# KeyboardPower.net
KiCad netlist of a schematic drawn in EAGLE
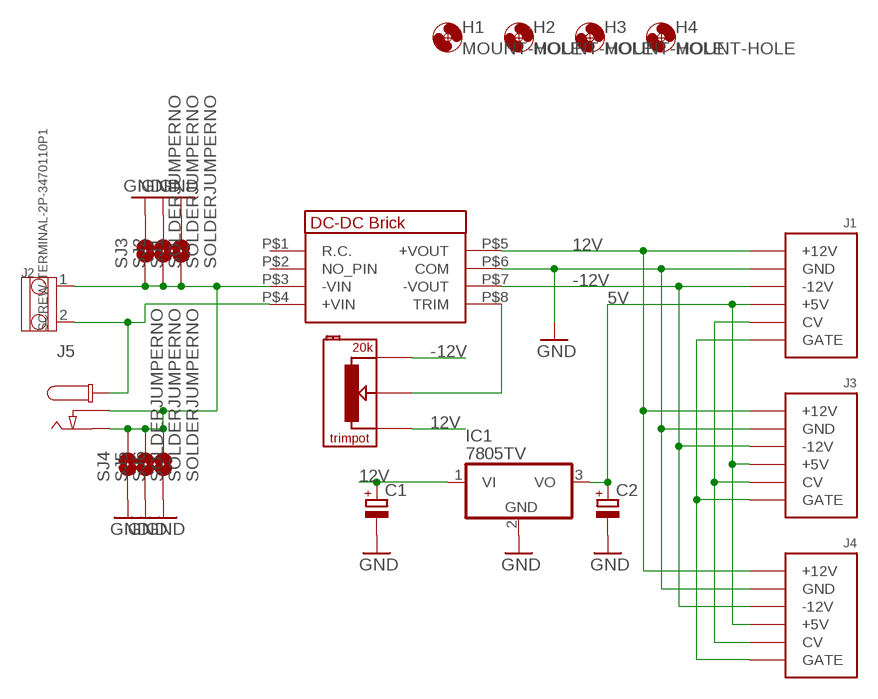
[diagram p0: schematic, sheet 1]

(export (version "E")
  (design (tool "Eeschema 10.0.6"))
  (components
    (comp (ref "C1")
      (value "CAPACITOR_POL-CASE_B")
      (footprint "eagle-import:CASE_B")
      (libsource (lib "eagle-import") (part "CAPACITOR_POL-CASE_B"))
    )
    (comp (ref "C2")
      (value "CAPACITOR_POL-CASE_B")
      (footprint "eagle-import:CASE_B")
      (libsource (lib "eagle-import") (part "CAPACITOR_POL-CASE_B"))
    )
    (comp (ref "H1")
      (value "MOUNT-HOLE")
      (footprint "eagle-import:3.2-NOMARKINGS-SMALLSAFEZONE")
      (libsource (lib "eagle-import") (part "MOUNT-HOLE"))
    )
    (comp (ref "H2")
      (value "MOUNT-HOLE")
      (footprint "eagle-import:3.2-NOMARKINGS-SMALLSAFEZONE")
      (libsource (lib "eagle-import") (part "MOUNT-HOLE"))
    )
    (comp (ref "H3")
      (value "MOUNT-HOLE")
      (footprint "eagle-import:3.2-NOMARKINGS-SMALLSAFEZONE")
      (libsource (lib "eagle-import") (part "MOUNT-HOLE"))
    )
    (comp (ref "H4")
      (value "MOUNT-HOLE")
      (footprint "eagle-import:3.2-NOMARKINGS-SMALLSAFEZONE")
      (libsource (lib "eagle-import") (part "MOUNT-HOLE"))
    )
    (comp (ref "IC1")
      (value "7805TV")
      (footprint "eagle-import:TO220V")
      (libsource (lib "eagle-import") (part "78TV05"))
    )
    (comp (ref "J1")
      (value "POWERSHROUDED")
      (footprint "eagle-import:POWER_16_SHROUDED")
      (libsource (lib "eagle-import") (part "POWERSHROUDED"))
    )
    (comp (ref "J2")
      (value "SCREW-TERMINAL-2P-3470110P1")
      (footprint "eagle-import:2P-5.0")
      (libsource (lib "eagle-import") (part "SCREW-TERMINAL-2P-3470110P1"))
    )
    (comp (ref "J3")
      (value "POWER_SHROUDED_NOTEXT")
      (footprint "eagle-import:POWER_16_SHROUDED_NOTEXT")
      (libsource (lib "eagle-import") (part "POWER_SHROUDED_NOTEXT"))
    )
    (comp (ref "J4")
      (value "POWER_SHROUDED_NOTEXT")
      (footprint "eagle-import:POWER_16_SHROUDED_NOTEXT")
      (libsource (lib "eagle-import") (part "POWER_SHROUDED_NOTEXT"))
    )
    (comp (ref "J5")
      (value "CON_DC_M-DC_PTH2")
      (footprint "eagle-import:DC_BARREL_JACK_PTH_2MM_2")
      (libsource (lib "eagle-import") (part "CON_DC_M-DC_PTH2"))
    )
    (comp (ref "R1")
      (value "20k")
      (footprint "eagle-import:TRIMPOT")
      (libsource (lib "eagle-import") (part "TRIMPOT"))
    )
    (comp (ref "SJ1")
      (value "SOLDERJUMPERNO")
      (footprint "eagle-import:SJ_2S-NO")
      (libsource (lib "eagle-import") (part "SOLDERJUMPERNO"))
    )
    (comp (ref "SJ2")
      (value "SOLDERJUMPERNO")
      (footprint "eagle-import:SJ_2S-NO")
      (libsource (lib "eagle-import") (part "SOLDERJUMPERNO"))
    )
    (comp (ref "SJ3")
      (value "SOLDERJUMPERNO")
      (footprint "eagle-import:SJ_2S-NO")
      (libsource (lib "eagle-import") (part "SOLDERJUMPERNO"))
    )
    (comp (ref "SJ4")
      (value "SOLDERJUMPERNO")
      (footprint "eagle-import:SJ_2S-NO")
      (libsource (lib "eagle-import") (part "SOLDERJUMPERNO"))
    )
    (comp (ref "SJ5")
      (value "SOLDERJUMPERNO")
      (footprint "eagle-import:SJ_2S-NO")
      (libsource (lib "eagle-import") (part "SOLDERJUMPERNO"))
    )
    (comp (ref "SJ6")
      (value "SOLDERJUMPERNO")
      (footprint "eagle-import:SJ_2S-NO")
      (libsource (lib "eagle-import") (part "SOLDERJUMPERNO"))
    )
    (comp (ref "U$1")
      (value "DKA30")
      (footprint "eagle-import:MEANWELL_DKA30")
      (libsource (lib "eagle-import") (part "DKA30"))
    )
  )
  (nets
    (net (code "1") (name "/-12V") (class "Default")
      (node (ref "J1") (pin "1") (pinfunction "-12V_1") (pintype "bidirectional"))
      (node (ref "J1") (pin "2") (pinfunction "-12V_2") (pintype "bidirectional"))
      (node (ref "J3") (pin "1") (pinfunction "-12V_1") (pintype "bidirectional"))
      (node (ref "J3") (pin "2") (pinfunction "-12V_2") (pintype "bidirectional"))
      (node (ref "J4") (pin "1") (pinfunction "-12V_1") (pintype "bidirectional"))
      (node (ref "J4") (pin "2") (pinfunction "-12V_2") (pintype "bidirectional"))
      (node (ref "R1") (pin "P$3") (pinfunction "P$3_P$3") (pintype "bidirectional"))
      (node (ref "U$1") (pin "P$7") (pinfunction "-VOUT_P$7") (pintype "bidirectional"))
    )
    (net (code "2") (name "/5V") (class "Default")
      (node (ref "C2") (pin "+") (pinfunction "+_+") (pintype "passive"))
      (node (ref "IC1") (pin "3") (pinfunction "VO_3") (pintype "passive"))
      (node (ref "J1") (pin "11") (pinfunction "+5V_11") (pintype "bidirectional"))
      (node (ref "J1") (pin "12") (pinfunction "+5V_12") (pintype "bidirectional"))
      (node (ref "J3") (pin "11") (pinfunction "+5V_11") (pintype "bidirectional"))
      (node (ref "J3") (pin "12") (pinfunction "+5V_12") (pintype "bidirectional"))
      (node (ref "J4") (pin "11") (pinfunction "+5V_11") (pintype "bidirectional"))
      (node (ref "J4") (pin "12") (pinfunction "+5V_12") (pintype "bidirectional"))
    )
    (net (code "3") (name "/12V") (class "Default")
      (node (ref "C1") (pin "+") (pinfunction "+_+") (pintype "passive"))
      (node (ref "IC1") (pin "1") (pinfunction "VI_1") (pintype "input"))
      (node (ref "J1") (pin "10") (pinfunction "+12V_10") (pintype "bidirectional"))
      (node (ref "J1") (pin "9") (pinfunction "+12V_9") (pintype "bidirectional"))
      (node (ref "J3") (pin "10") (pinfunction "+12V_10") (pintype "bidirectional"))
      (node (ref "J3") (pin "9") (pinfunction "+12V_9") (pintype "bidirectional"))
      (node (ref "J4") (pin "10") (pinfunction "+12V_10") (pintype "bidirectional"))
      (node (ref "J4") (pin "9") (pinfunction "+12V_9") (pintype "bidirectional"))
      (node (ref "R1") (pin "P$1") (pinfunction "P$1_P$1") (pintype "bidirectional"))
      (node (ref "U$1") (pin "P$5") (pinfunction "+VOUT_P$5") (pintype "bidirectional"))
    )
    (net (code "4") (name "GND") (class "Default")
      (node (ref "C1") (pin "-") (pinfunction "-_-") (pintype "passive"))
      (node (ref "C2") (pin "-") (pinfunction "-_-") (pintype "passive"))
      (node (ref "IC1") (pin "2") (pinfunction "GND_2") (pintype "passive"))
      (node (ref "J1") (pin "3") (pinfunction "GND_3") (pintype "bidirectional"))
      (node (ref "J1") (pin "4") (pinfunction "GND_4") (pintype "bidirectional"))
      (node (ref "J1") (pin "5") (pinfunction "GND_5") (pintype "bidirectional"))
      (node (ref "J1") (pin "6") (pinfunction "GND_6") (pintype "bidirectional"))
      (node (ref "J1") (pin "7") (pinfunction "GND_7") (pintype "bidirectional"))
      (node (ref "J1") (pin "8") (pinfunction "GND_8") (pintype "bidirectional"))
      (node (ref "J3") (pin "3") (pinfunction "GND_3") (pintype "bidirectional"))
      (node (ref "J3") (pin "4") (pinfunction "GND_4") (pintype "bidirectional"))
      (node (ref "J3") (pin "5") (pinfunction "GND_5") (pintype "bidirectional"))
      (node (ref "J3") (pin "6") (pinfunction "GND_6") (pintype "bidirectional"))
      (node (ref "J3") (pin "7") (pinfunction "GND_7") (pintype "bidirectional"))
      (node (ref "J3") (pin "8") (pinfunction "GND_8") (pintype "bidirectional"))
      (node (ref "J4") (pin "3") (pinfunction "GND_3") (pintype "bidirectional"))
      (node (ref "J4") (pin "4") (pinfunction "GND_4") (pintype "bidirectional"))
      (node (ref "J4") (pin "5") (pinfunction "GND_5") (pintype "bidirectional"))
      (node (ref "J4") (pin "6") (pinfunction "GND_6") (pintype "bidirectional"))
      (node (ref "J4") (pin "7") (pinfunction "GND_7") (pintype "bidirectional"))
      (node (ref "J4") (pin "8") (pinfunction "GND_8") (pintype "bidirectional"))
      (node (ref "SJ1") (pin "2") (pinfunction "2_2") (pintype "passive"))
      (node (ref "SJ2") (pin "2") (pinfunction "2_2") (pintype "passive"))
      (node (ref "SJ3") (pin "2") (pinfunction "2_2") (pintype "passive"))
      (node (ref "SJ4") (pin "1") (pinfunction "1_1") (pintype "passive"))
      (node (ref "SJ5") (pin "1") (pinfunction "1_1") (pintype "passive"))
      (node (ref "SJ6") (pin "1") (pinfunction "1_1") (pintype "passive"))
      (node (ref "U$1") (pin "P$6") (pinfunction "COM_P$6") (pintype "bidirectional"))
    )
    (net (code "5") (name "Net-(J1-CV-Pad13)") (class "Default")
      (node (ref "J1") (pin "13") (pinfunction "CV_13") (pintype "bidirectional"))
      (node (ref "J1") (pin "14") (pinfunction "CV_14") (pintype "bidirectional"))
      (node (ref "J3") (pin "13") (pinfunction "CV_13") (pintype "bidirectional"))
      (node (ref "J3") (pin "14") (pinfunction "CV_14") (pintype "bidirectional"))
      (node (ref "J4") (pin "13") (pinfunction "CV_13") (pintype "bidirectional"))
      (node (ref "J4") (pin "14") (pinfunction "CV_14") (pintype "bidirectional"))
    )
    (net (code "6") (name "Net-(J1-GATE-Pad15)") (class "Default")
      (node (ref "J1") (pin "15") (pinfunction "GATE_15") (pintype "bidirectional"))
      (node (ref "J1") (pin "16") (pinfunction "GATE_16") (pintype "bidirectional"))
      (node (ref "J3") (pin "15") (pinfunction "GATE_15") (pintype "bidirectional"))
      (node (ref "J3") (pin "16") (pinfunction "GATE_16") (pintype "bidirectional"))
      (node (ref "J4") (pin "15") (pinfunction "GATE_15") (pintype "bidirectional"))
      (node (ref "J4") (pin "16") (pinfunction "GATE_16") (pintype "bidirectional"))
    )
    (net (code "7") (name "Net-(J5-P2)") (class "Default")
      (node (ref "J2") (pin "1") (pinfunction "1_1") (pintype "bidirectional"))
      (node (ref "J5") (pin "P2") (pinfunction "P3_P2") (pintype "passive"))
      (node (ref "J5") (pin "P3") (pinfunction "P2_P3") (pintype "passive"))
      (node (ref "SJ1") (pin "1") (pinfunction "1_1") (pintype "passive"))
      (node (ref "SJ2") (pin "1") (pinfunction "1_1") (pintype "passive"))
      (node (ref "SJ3") (pin "1") (pinfunction "1_1") (pintype "passive"))
      (node (ref "SJ4") (pin "2") (pinfunction "2_2") (pintype "passive"))
      (node (ref "SJ5") (pin "2") (pinfunction "2_2") (pintype "passive"))
      (node (ref "SJ6") (pin "2") (pinfunction "2_2") (pintype "passive"))
      (node (ref "U$1") (pin "P$3") (pinfunction "-VIN_P$3") (pintype "bidirectional"))
    )
    (net (code "8") (name "Net-(U$1-+VIN)") (class "Default")
      (node (ref "J2") (pin "2") (pinfunction "2_2") (pintype "bidirectional"))
      (node (ref "J5") (pin "P1") (pinfunction "P1_P1") (pintype "passive"))
      (node (ref "U$1") (pin "P$4") (pinfunction "+VIN_P$4") (pintype "bidirectional"))
    )
    (net (code "9") (name "Net-(U$1-TRIM)") (class "Default")
      (node (ref "R1") (pin "P$2") (pinfunction "P$2_P$2") (pintype "bidirectional"))
      (node (ref "U$1") (pin "P$8") (pinfunction "TRIM_P$8") (pintype "bidirectional"))
    )
    (net (code "10") (name "unconnected-(U$1-NO_PIN-PadP$2)") (class "Default")
      (node (ref "U$1") (pin "P$2") (pinfunction "NO_PIN_P$2") (pintype "bidirectional"))
    )
    (net (code "11") (name "unconnected-(U$1-R.C.-PadP$1)") (class "Default")
      (node (ref "U$1") (pin "P$1") (pinfunction "R.C._P$1") (pintype "bidirectional"))
    )
  )
)
